# Nakuja_Power.net
KiCad netlist of a schematic drawn in EasyEDA
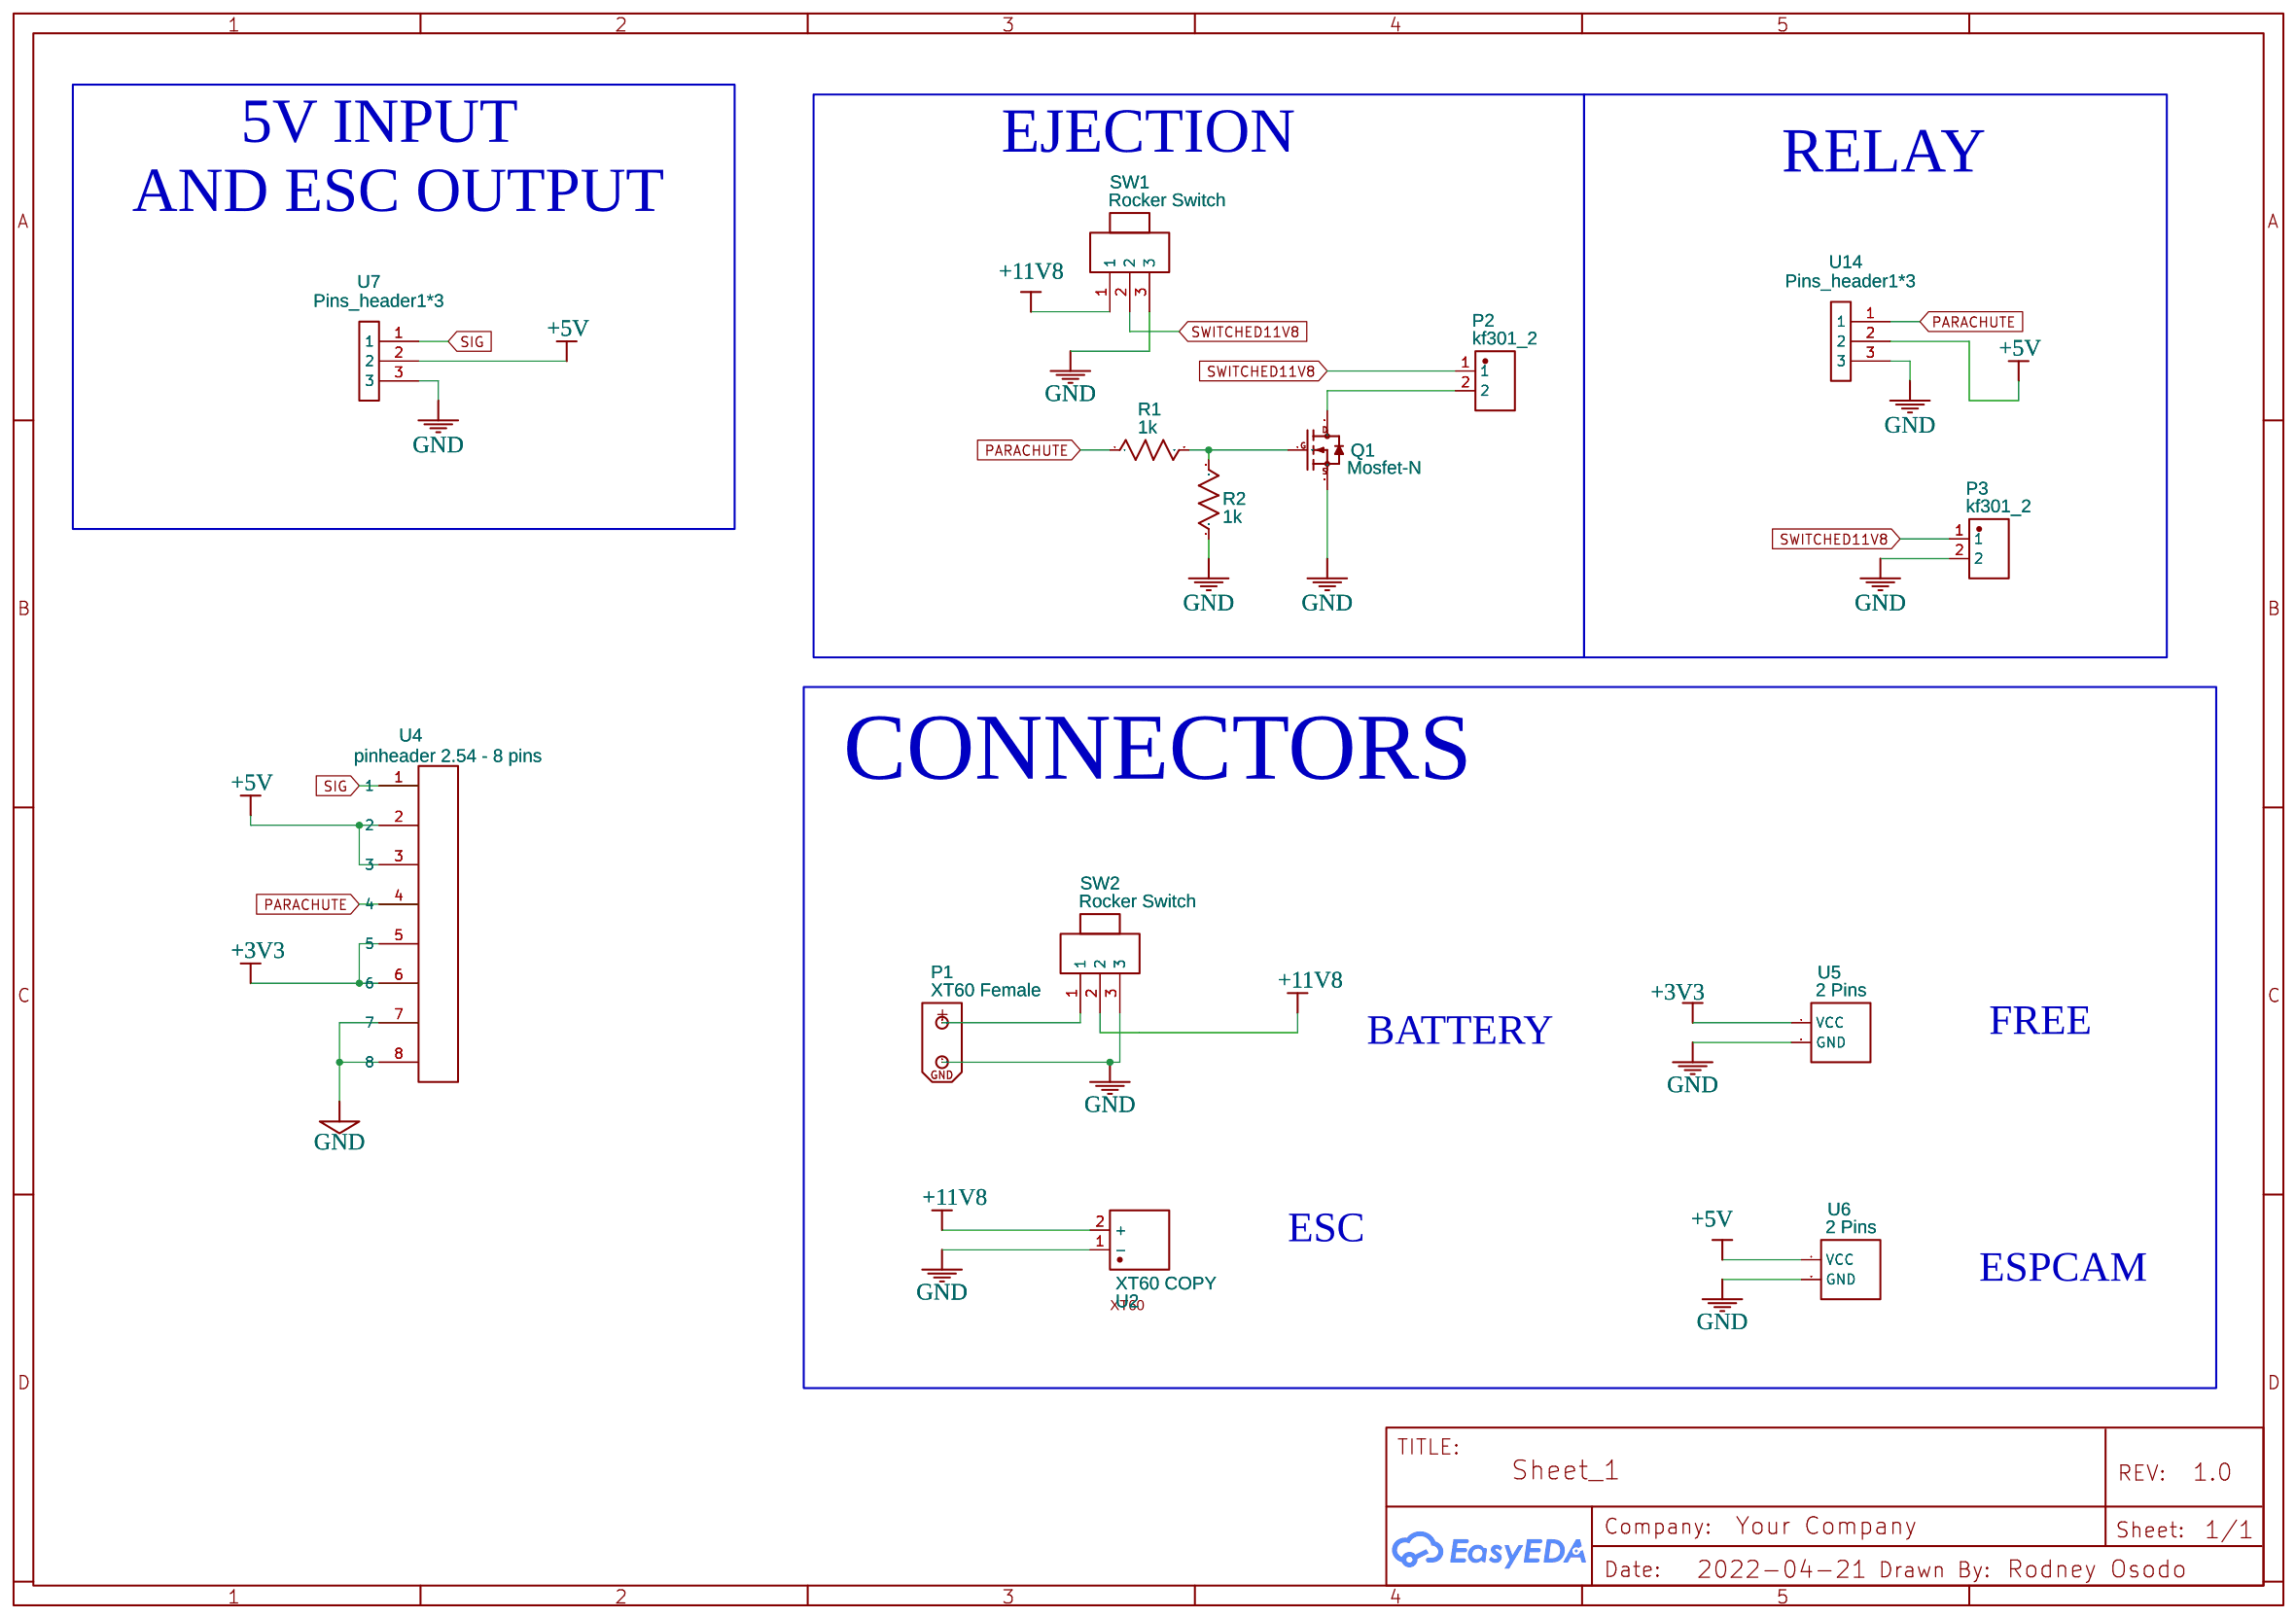
[diagram p0: schematic sheet]

(export (version "E")
  (design (tool "Eeschema 10.0.6"))
  (components
    (comp (ref "P1")
      (value "XT60 Female")
      (fields (field (name "BOM_Manufacturer Part") "XT60-F"))
      (libsource (lib "") (part "XT60 Female"))
    )
    (comp (ref "P2")
      (value "kf301_2")
      (fields (field (name "BOM_Supplier Part") "C33435"))
      (libsource (lib "") (part "kf301_2"))
    )
    (comp (ref "P3")
      (value "kf301_2")
      (fields (field (name "BOM_Supplier Part") "C33435"))
      (libsource (lib "") (part "kf301_2"))
    )
    (comp (ref "Q1") (value "Mosfet-N") (libsource (lib "") (part "Mosfet-N")))
    (comp (ref "R1") (value "1k") (libsource (lib "") (part "R_AXIAL-0.6_US")))
    (comp (ref "R2") (value "1k") (libsource (lib "") (part "R_AXIAL-0.6_US_1")))
    (comp (ref "SW1") (value "Rocker Switch") (libsource (lib "") (part "Rocker Switch")))
    (comp (ref "SW2") (value "Rocker Switch") (libsource (lib "") (part "Rocker Switch")))
    (comp (ref "U2") (value "XT60 COPY") (libsource (lib "") (part "XT60 COPY")))
    (comp (ref "U4") (value "pinheader 2.54 - 8 pins") (libsource (lib "") (part "pinheader 2.54 - 8 pins")))
    (comp (ref "U5") (value "2 Pins") (libsource (lib "") (part "2 Pins")))
    (comp (ref "U6") (value "2 Pins") (libsource (lib "") (part "2 Pins")))
    (comp (ref "U7") (value "Pins_header1*3") (libsource (lib "") (part "Pins_header1*3")))
    (comp (ref "U14") (value "Pins_header1*3") (libsource (lib "") (part "Pins_header1*3")))
  )
  (nets
    (net (code "1") (name "+3V3") (class "Default")
      (node (ref "U4") (pin "5") (pinfunction "5_5") (pintype "unspecified"))
      (node (ref "U4") (pin "6") (pinfunction "6_6") (pintype "unspecified"))
      (node (ref "U5") (pin "1") (pinfunction "VCC_1") (pintype "unspecified"))
    )
    (net (code "2") (name "+5V") (class "Default")
      (node (ref "U14") (pin "2") (pinfunction "2_2") (pintype "unspecified"))
      (node (ref "U4") (pin "2") (pinfunction "2_2") (pintype "unspecified"))
      (node (ref "U4") (pin "3") (pinfunction "3_3") (pintype "unspecified"))
      (node (ref "U6") (pin "1") (pinfunction "VCC_1") (pintype "unspecified"))
      (node (ref "U7") (pin "2") (pinfunction "2_2") (pintype "unspecified"))
    )
    (net (code "3") (name "+11V8") (class "Default")
      (node (ref "SW1") (pin "1") (pinfunction "1_1") (pintype "unspecified"))
      (node (ref "SW2") (pin "2") (pinfunction "2_2") (pintype "unspecified"))
      (node (ref "U2") (pin "2") (pinfunction "+_2") (pintype "unspecified"))
    )
    (net (code "4") (name "GND") (class "Default")
      (node (ref "P1") (pin "1") (pinfunction "1_1") (pintype "unspecified"))
      (node (ref "P3") (pin "2") (pinfunction "2_2") (pintype "unspecified"))
      (node (ref "Q1") (pin "3") (pinfunction "S_3") (pintype "unspecified"))
      (node (ref "R2") (pin "1") (pinfunction "1_1") (pintype "unspecified"))
      (node (ref "SW1") (pin "3") (pinfunction "3_3") (pintype "unspecified"))
      (node (ref "SW2") (pin "3") (pinfunction "3_3") (pintype "unspecified"))
      (node (ref "U14") (pin "3") (pinfunction "3_3") (pintype "unspecified"))
      (node (ref "U2") (pin "1") (pinfunction "-_1") (pintype "unspecified"))
      (node (ref "U4") (pin "7") (pinfunction "7_7") (pintype "unspecified"))
      (node (ref "U4") (pin "8") (pinfunction "8_8") (pintype "unspecified"))
      (node (ref "U5") (pin "2") (pinfunction "GND_2") (pintype "unspecified"))
      (node (ref "U6") (pin "2") (pinfunction "GND_2") (pintype "unspecified"))
      (node (ref "U7") (pin "3") (pinfunction "3_3") (pintype "unspecified"))
    )
    (net (code "5") (name "Net-(P1-Pad2)") (class "Default")
      (node (ref "P1") (pin "2") (pinfunction "2_2") (pintype "unspecified"))
      (node (ref "SW2") (pin "1") (pinfunction "1_1") (pintype "unspecified"))
    )
    (net (code "6") (name "Net-(Q1-D)") (class "Default")
      (node (ref "P2") (pin "2") (pinfunction "2_2") (pintype "unspecified"))
      (node (ref "Q1") (pin "2") (pinfunction "D_2") (pintype "unspecified"))
    )
    (net (code "7") (name "Net-(Q1-G)") (class "Default")
      (node (ref "Q1") (pin "1") (pinfunction "G_1") (pintype "unspecified"))
      (node (ref "R1") (pin "2") (pinfunction "2_2") (pintype "unspecified"))
      (node (ref "R2") (pin "2") (pinfunction "2_2") (pintype "unspecified"))
    )
    (net (code "8") (name "PARACHUTE") (class "Default")
      (node (ref "R1") (pin "1") (pinfunction "1_1") (pintype "unspecified"))
      (node (ref "U14") (pin "1") (pinfunction "1_1") (pintype "unspecified"))
      (node (ref "U4") (pin "4") (pinfunction "4_4") (pintype "unspecified"))
    )
    (net (code "9") (name "SIG") (class "Default")
      (node (ref "U4") (pin "1") (pinfunction "1_1") (pintype "unspecified"))
      (node (ref "U7") (pin "1") (pinfunction "1_1") (pintype "unspecified"))
    )
    (net (code "10") (name "SWITCHED11V8") (class "Default")
      (node (ref "P2") (pin "1") (pinfunction "1_1") (pintype "unspecified"))
      (node (ref "P3") (pin "1") (pinfunction "1_1") (pintype "unspecified"))
      (node (ref "SW1") (pin "2") (pinfunction "2_2") (pintype "unspecified"))
    )
  )
)
